# GPIO_mcu_plis.net
KiCad netlist of a schematic drawn in Altium Designer
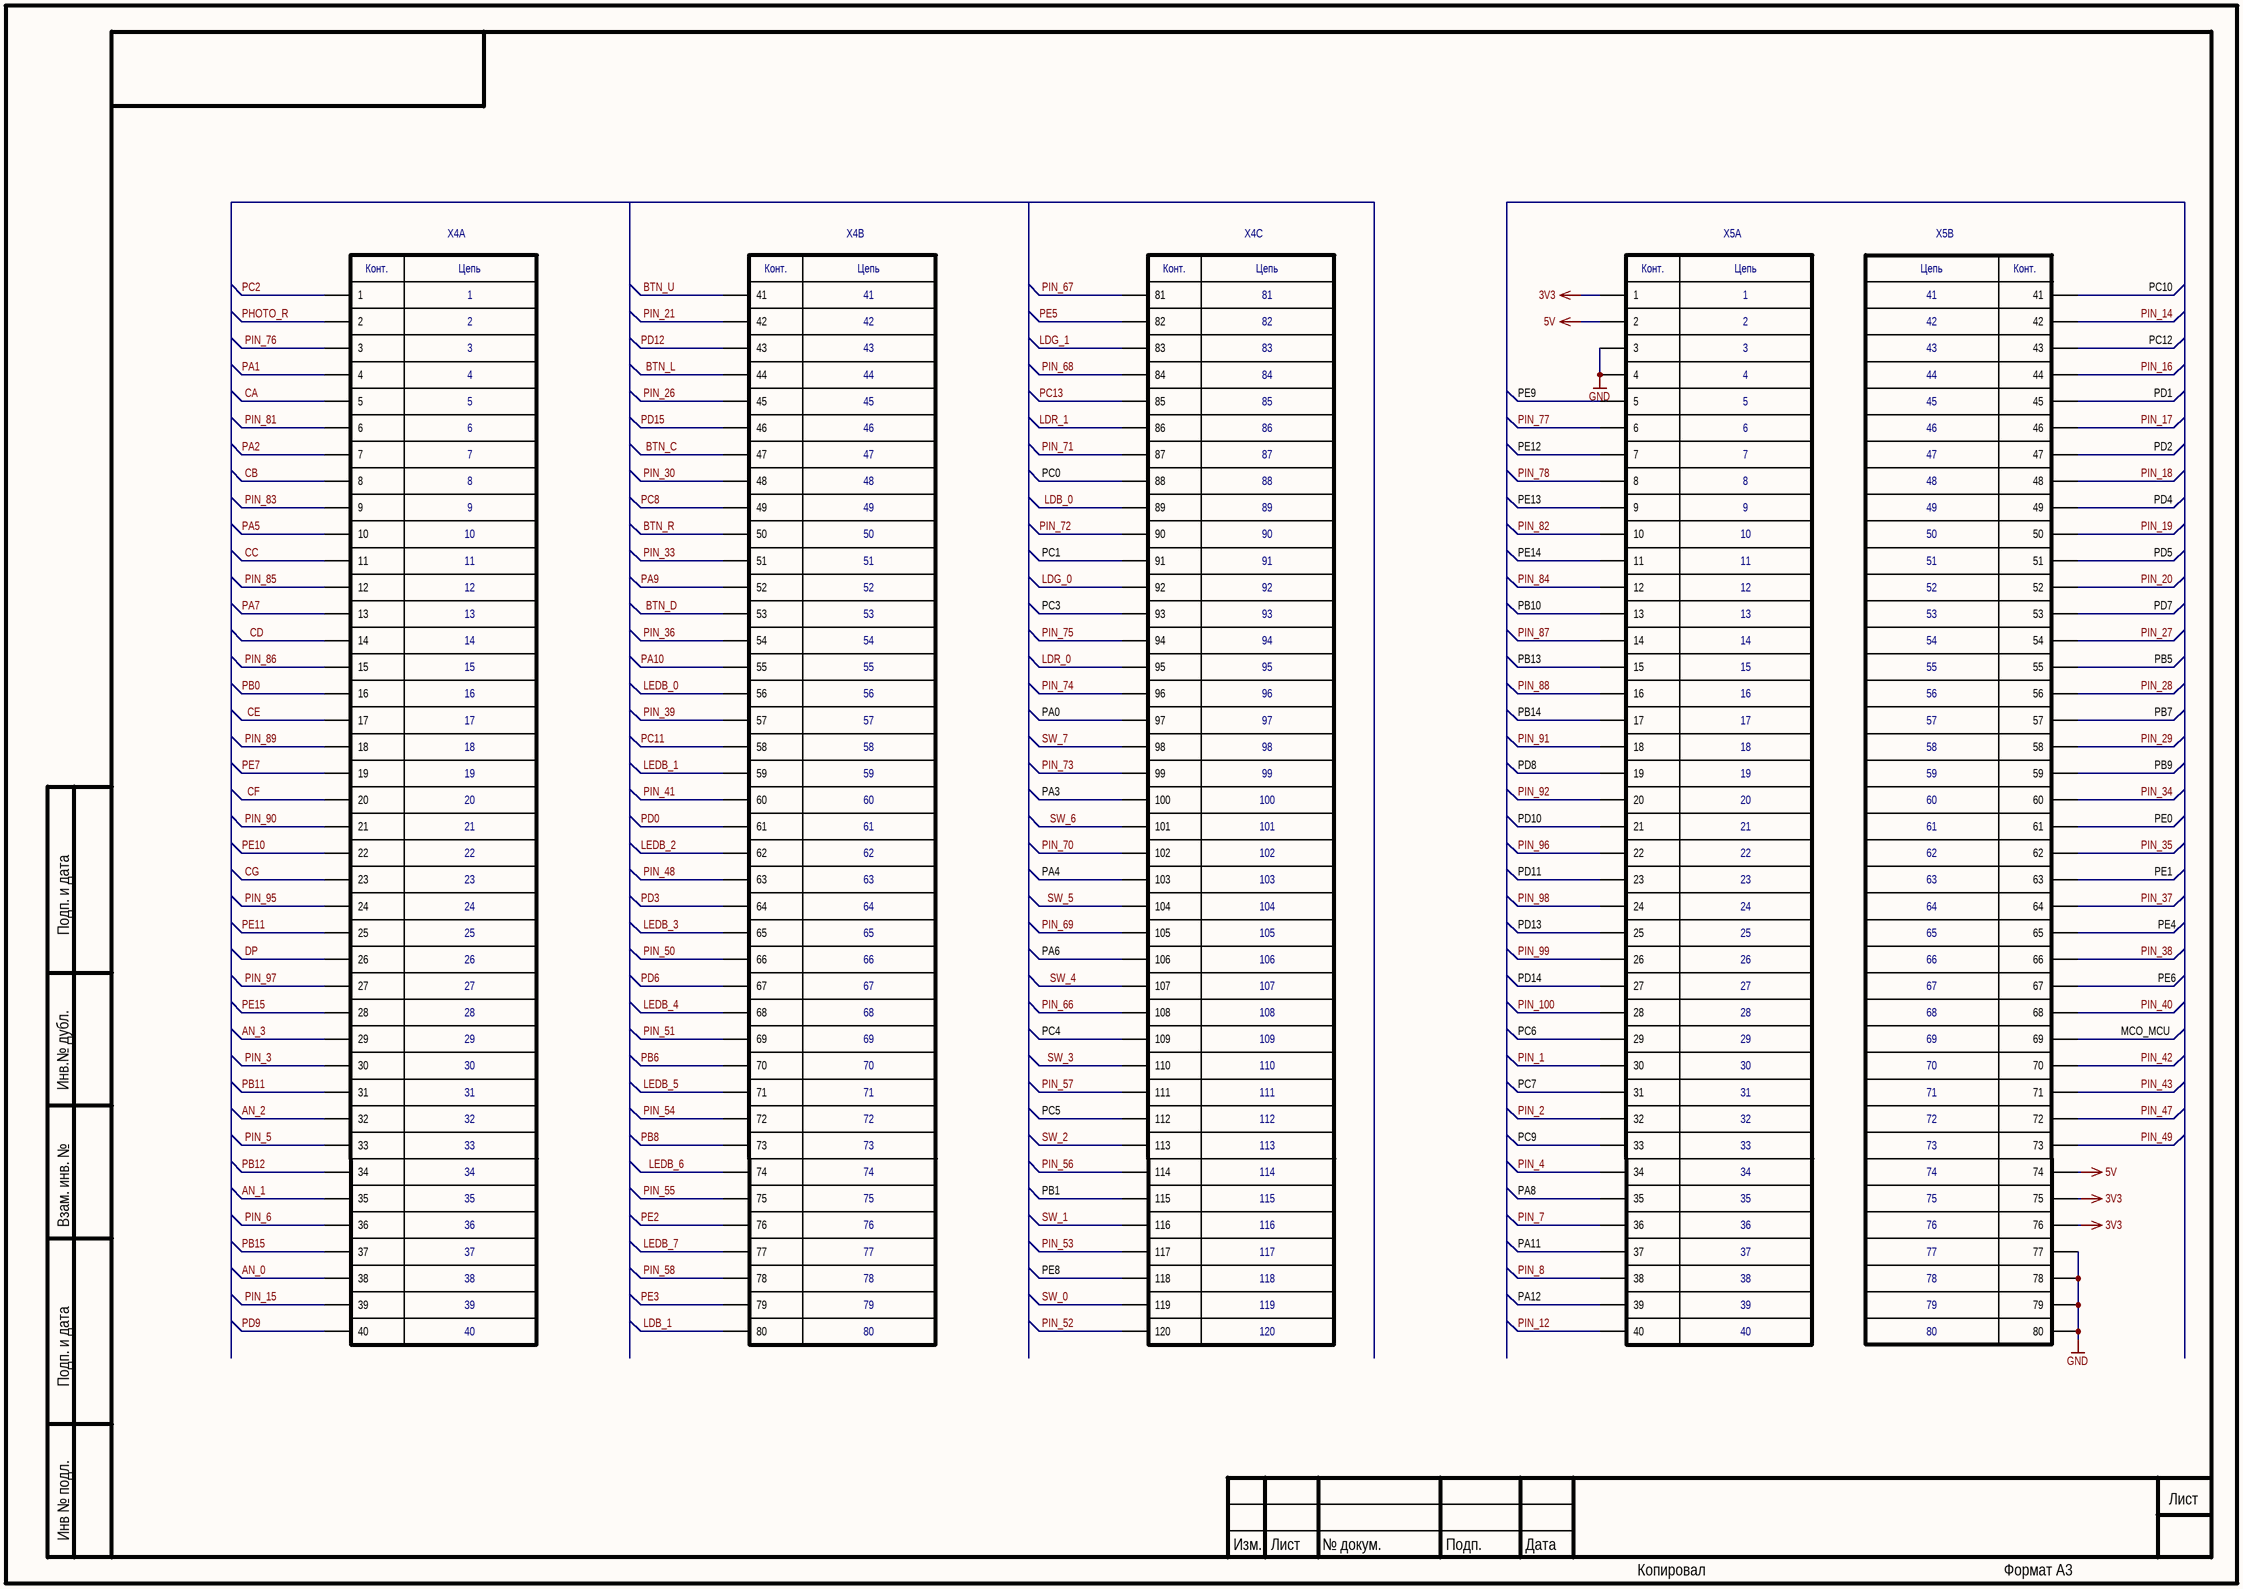
[diagram p0: GPIO_mcu_plis.SchDoc]

(export (version "E")
  (design (tool "Eeschema 10.0.6"))
  (components
    (comp (ref "X4")
      (value "KONT_POLE_MEZ")
      (footprint "Lisaveta_PCB:PLT-120")
      (libsource (lib "Lisaveta") (part "KONT_POLE_120"))
    )
    (comp (ref "X5")
      (value "KONT_POLE_MEZ")
      (footprint "PLD-80")
      (libsource (lib "Lisaveta") (part "KONT_POLE_80"))
    )
  )
  (nets
    (net (code "1") (name "/AN_0") (class "Default")
      (node (ref "X4") (pin "38") (pinfunction "38_38") (pintype "passive"))
    )
    (net (code "2") (name "/AN_1") (class "Default")
      (node (ref "X4") (pin "35") (pinfunction "35_35") (pintype "passive"))
    )
    (net (code "3") (name "/AN_2") (class "Default")
      (node (ref "X4") (pin "32") (pinfunction "32_32") (pintype "passive"))
    )
    (net (code "4") (name "/AN_3") (class "Default")
      (node (ref "X4") (pin "29") (pinfunction "29_29") (pintype "passive"))
    )
    (net (code "5") (name "/BTN_C") (class "Default")
      (node (ref "X4") (pin "47") (pinfunction "47_47") (pintype "passive"))
    )
    (net (code "6") (name "/BTN_D") (class "Default")
      (node (ref "X4") (pin "53") (pinfunction "53_53") (pintype "passive"))
    )
    (net (code "7") (name "/BTN_L") (class "Default")
      (node (ref "X4") (pin "44") (pinfunction "44_44") (pintype "passive"))
    )
    (net (code "8") (name "/BTN_R") (class "Default")
      (node (ref "X4") (pin "50") (pinfunction "50_50") (pintype "passive"))
    )
    (net (code "9") (name "/BTN_U") (class "Default")
      (node (ref "X4") (pin "41") (pinfunction "41_41") (pintype "passive"))
    )
    (net (code "10") (name "/CA") (class "Default")
      (node (ref "X4") (pin "5") (pinfunction "5_5") (pintype "passive"))
    )
    (net (code "11") (name "/CB") (class "Default")
      (node (ref "X4") (pin "8") (pinfunction "8_8") (pintype "passive"))
    )
    (net (code "12") (name "/CC") (class "Default")
      (node (ref "X4") (pin "11") (pinfunction "11_11") (pintype "passive"))
    )
    (net (code "13") (name "/CD") (class "Default")
      (node (ref "X4") (pin "14") (pinfunction "14_14") (pintype "passive"))
    )
    (net (code "14") (name "/CE") (class "Default")
      (node (ref "X4") (pin "17") (pinfunction "17_17") (pintype "passive"))
    )
    (net (code "15") (name "/CF") (class "Default")
      (node (ref "X4") (pin "20") (pinfunction "20_20") (pintype "passive"))
    )
    (net (code "16") (name "/CG") (class "Default")
      (node (ref "X4") (pin "23") (pinfunction "23_23") (pintype "passive"))
    )
    (net (code "17") (name "/DP") (class "Default")
      (node (ref "X4") (pin "26") (pinfunction "26_26") (pintype "passive"))
    )
    (net (code "18") (name "/LDB_0") (class "Default")
      (node (ref "X4") (pin "89") (pinfunction "89_89") (pintype "passive"))
    )
    (net (code "19") (name "/LDB_1") (class "Default")
      (node (ref "X4") (pin "80") (pinfunction "80_80") (pintype "passive"))
    )
    (net (code "20") (name "/LDG_0") (class "Default")
      (node (ref "X4") (pin "92") (pinfunction "92_92") (pintype "passive"))
    )
    (net (code "21") (name "/LDG_1") (class "Default")
      (node (ref "X4") (pin "83") (pinfunction "83_83") (pintype "passive"))
    )
    (net (code "22") (name "/LDR_0") (class "Default")
      (node (ref "X4") (pin "95") (pinfunction "95_95") (pintype "passive"))
    )
    (net (code "23") (name "/LDR_1") (class "Default")
      (node (ref "X4") (pin "86") (pinfunction "86_86") (pintype "passive"))
    )
    (net (code "24") (name "/LEDB_0") (class "Default")
      (node (ref "X4") (pin "56") (pinfunction "56_56") (pintype "passive"))
    )
    (net (code "25") (name "/LEDB_1") (class "Default")
      (node (ref "X4") (pin "59") (pinfunction "59_59") (pintype "passive"))
    )
    (net (code "26") (name "/LEDB_2") (class "Default")
      (node (ref "X4") (pin "62") (pinfunction "62_62") (pintype "passive"))
    )
    (net (code "27") (name "/LEDB_3") (class "Default")
      (node (ref "X4") (pin "65") (pinfunction "65_65") (pintype "passive"))
    )
    (net (code "28") (name "/LEDB_4") (class "Default")
      (node (ref "X4") (pin "68") (pinfunction "68_68") (pintype "passive"))
    )
    (net (code "29") (name "/LEDB_5") (class "Default")
      (node (ref "X4") (pin "71") (pinfunction "71_71") (pintype "passive"))
    )
    (net (code "30") (name "/LEDB_6") (class "Default")
      (node (ref "X4") (pin "74") (pinfunction "74_74") (pintype "passive"))
    )
    (net (code "31") (name "/LEDB_7") (class "Default")
      (node (ref "X4") (pin "77") (pinfunction "77_77") (pintype "passive"))
    )
    (net (code "32") (name "/MCO_MCU") (class "Default")
      (node (ref "X5") (pin "69") (pinfunction "69_69") (pintype "passive"))
    )
    (net (code "33") (name "/PA0") (class "Default")
      (node (ref "X4") (pin "97") (pinfunction "97_97") (pintype "passive"))
    )
    (net (code "34") (name "/PA1") (class "Default")
      (node (ref "X4") (pin "4") (pinfunction "4_4") (pintype "passive"))
    )
    (net (code "35") (name "/PA2") (class "Default")
      (node (ref "X4") (pin "7") (pinfunction "7_7") (pintype "passive"))
    )
    (net (code "36") (name "/PA3") (class "Default")
      (node (ref "X4") (pin "100") (pinfunction "100_100") (pintype "passive"))
    )
    (net (code "37") (name "/PA4") (class "Default")
      (node (ref "X4") (pin "103") (pinfunction "103_103") (pintype "passive"))
    )
    (net (code "38") (name "/PA5") (class "Default")
      (node (ref "X4") (pin "10") (pinfunction "10_10") (pintype "passive"))
    )
    (net (code "39") (name "/PA6") (class "Default")
      (node (ref "X4") (pin "106") (pinfunction "106_106") (pintype "passive"))
    )
    (net (code "40") (name "/PA7") (class "Default")
      (node (ref "X4") (pin "13") (pinfunction "13_13") (pintype "passive"))
    )
    (net (code "41") (name "/PA8") (class "Default")
      (node (ref "X5") (pin "35") (pinfunction "35_35") (pintype "passive"))
    )
    (net (code "42") (name "/PA9") (class "Default")
      (node (ref "X4") (pin "52") (pinfunction "52_52") (pintype "passive"))
    )
    (net (code "43") (name "/PA10") (class "Default")
      (node (ref "X4") (pin "55") (pinfunction "55_55") (pintype "passive"))
    )
    (net (code "44") (name "/PA11") (class "Default")
      (node (ref "X5") (pin "37") (pinfunction "37_37") (pintype "passive"))
    )
    (net (code "45") (name "/PA12") (class "Default")
      (node (ref "X5") (pin "39") (pinfunction "39_39") (pintype "passive"))
    )
    (net (code "46") (name "/PB0") (class "Default")
      (node (ref "X4") (pin "16") (pinfunction "16_16") (pintype "passive"))
    )
    (net (code "47") (name "/PB1") (class "Default")
      (node (ref "X4") (pin "115") (pinfunction "115_115") (pintype "passive"))
    )
    (net (code "48") (name "/PB5") (class "Default")
      (node (ref "X5") (pin "55") (pinfunction "55_55") (pintype "passive"))
    )
    (net (code "49") (name "/PB6") (class "Default")
      (node (ref "X4") (pin "70") (pinfunction "70_70") (pintype "passive"))
    )
    (net (code "50") (name "/PB7") (class "Default")
      (node (ref "X5") (pin "57") (pinfunction "57_57") (pintype "passive"))
    )
    (net (code "51") (name "/PB8") (class "Default")
      (node (ref "X4") (pin "73") (pinfunction "73_73") (pintype "passive"))
    )
    (net (code "52") (name "/PB9") (class "Default")
      (node (ref "X5") (pin "59") (pinfunction "59_59") (pintype "passive"))
    )
    (net (code "53") (name "/PB10") (class "Default")
      (node (ref "X5") (pin "13") (pinfunction "13_13") (pintype "passive"))
    )
    (net (code "54") (name "/PB11") (class "Default")
      (node (ref "X4") (pin "31") (pinfunction "31_31") (pintype "passive"))
    )
    (net (code "55") (name "/PB12") (class "Default")
      (node (ref "X4") (pin "34") (pinfunction "34_34") (pintype "passive"))
    )
    (net (code "56") (name "/PB13") (class "Default")
      (node (ref "X5") (pin "15") (pinfunction "15_15") (pintype "passive"))
    )
    (net (code "57") (name "/PB14") (class "Default")
      (node (ref "X5") (pin "17") (pinfunction "17_17") (pintype "passive"))
    )
    (net (code "58") (name "/PB15") (class "Default")
      (node (ref "X4") (pin "37") (pinfunction "37_37") (pintype "passive"))
    )
    (net (code "59") (name "/PC0") (class "Default")
      (node (ref "X4") (pin "88") (pinfunction "88_88") (pintype "passive"))
    )
    (net (code "60") (name "/PC1") (class "Default")
      (node (ref "X4") (pin "91") (pinfunction "91_91") (pintype "passive"))
    )
    (net (code "61") (name "/PC2") (class "Default")
      (node (ref "X4") (pin "1") (pinfunction "1_1") (pintype "passive"))
    )
    (net (code "62") (name "/PC3") (class "Default")
      (node (ref "X4") (pin "93") (pinfunction "93_93") (pintype "passive"))
    )
    (net (code "63") (name "/PC4") (class "Default")
      (node (ref "X4") (pin "109") (pinfunction "109_109") (pintype "passive"))
    )
    (net (code "64") (name "/PC5") (class "Default")
      (node (ref "X4") (pin "112") (pinfunction "112_112") (pintype "passive"))
    )
    (net (code "65") (name "/PC6") (class "Default")
      (node (ref "X5") (pin "29") (pinfunction "29_29") (pintype "passive"))
    )
    (net (code "66") (name "/PC7") (class "Default")
      (node (ref "X5") (pin "31") (pinfunction "31_31") (pintype "passive"))
    )
    (net (code "67") (name "/PC8") (class "Default")
      (node (ref "X4") (pin "49") (pinfunction "49_49") (pintype "passive"))
    )
    (net (code "68") (name "/PC9") (class "Default")
      (node (ref "X5") (pin "33") (pinfunction "33_33") (pintype "passive"))
    )
    (net (code "69") (name "/PC10") (class "Default")
      (node (ref "X5") (pin "41") (pinfunction "41_41") (pintype "passive"))
    )
    (net (code "70") (name "/PC11") (class "Default")
      (node (ref "X4") (pin "58") (pinfunction "58_58") (pintype "passive"))
    )
    (net (code "71") (name "/PC12") (class "Default")
      (node (ref "X5") (pin "43") (pinfunction "43_43") (pintype "passive"))
    )
    (net (code "72") (name "/PC13") (class "Default")
      (node (ref "X4") (pin "85") (pinfunction "85_85") (pintype "passive"))
    )
    (net (code "73") (name "/PD0") (class "Default")
      (node (ref "X4") (pin "61") (pinfunction "61_61") (pintype "passive"))
    )
    (net (code "74") (name "/PD1") (class "Default")
      (node (ref "X5") (pin "45") (pinfunction "45_45") (pintype "passive"))
    )
    (net (code "75") (name "/PD2") (class "Default")
      (node (ref "X5") (pin "47") (pinfunction "47_47") (pintype "passive"))
    )
    (net (code "76") (name "/PD3") (class "Default")
      (node (ref "X4") (pin "64") (pinfunction "64_64") (pintype "passive"))
    )
    (net (code "77") (name "/PD4") (class "Default")
      (node (ref "X5") (pin "49") (pinfunction "49_49") (pintype "passive"))
    )
    (net (code "78") (name "/PD5") (class "Default")
      (node (ref "X5") (pin "51") (pinfunction "51_51") (pintype "passive"))
    )
    (net (code "79") (name "/PD6") (class "Default")
      (node (ref "X4") (pin "67") (pinfunction "67_67") (pintype "passive"))
    )
    (net (code "80") (name "/PD7") (class "Default")
      (node (ref "X5") (pin "53") (pinfunction "53_53") (pintype "passive"))
    )
    (net (code "81") (name "/PD8") (class "Default")
      (node (ref "X5") (pin "19") (pinfunction "19_19") (pintype "passive"))
    )
    (net (code "82") (name "/PD9") (class "Default")
      (node (ref "X4") (pin "40") (pinfunction "40_40") (pintype "passive"))
    )
    (net (code "83") (name "/PD10") (class "Default")
      (node (ref "X5") (pin "21") (pinfunction "21_21") (pintype "passive"))
    )
    (net (code "84") (name "/PD11") (class "Default")
      (node (ref "X5") (pin "23") (pinfunction "23_23") (pintype "passive"))
    )
    (net (code "85") (name "/PD12") (class "Default")
      (node (ref "X4") (pin "43") (pinfunction "43_43") (pintype "passive"))
    )
    (net (code "86") (name "/PD13") (class "Default")
      (node (ref "X5") (pin "25") (pinfunction "25_25") (pintype "passive"))
    )
    (net (code "87") (name "/PD14") (class "Default")
      (node (ref "X5") (pin "27") (pinfunction "27_27") (pintype "passive"))
    )
    (net (code "88") (name "/PD15") (class "Default")
      (node (ref "X4") (pin "46") (pinfunction "46_46") (pintype "passive"))
    )
    (net (code "89") (name "/PE0") (class "Default")
      (node (ref "X5") (pin "61") (pinfunction "61_61") (pintype "passive"))
    )
    (net (code "90") (name "/PE1") (class "Default")
      (node (ref "X5") (pin "63") (pinfunction "63_63") (pintype "passive"))
    )
    (net (code "91") (name "/PE2") (class "Default")
      (node (ref "X4") (pin "76") (pinfunction "76_76") (pintype "passive"))
    )
    (net (code "92") (name "/PE3") (class "Default")
      (node (ref "X4") (pin "79") (pinfunction "79_79") (pintype "passive"))
    )
    (net (code "93") (name "/PE4") (class "Default")
      (node (ref "X5") (pin "65") (pinfunction "65_65") (pintype "passive"))
    )
    (net (code "94") (name "/PE5") (class "Default")
      (node (ref "X4") (pin "82") (pinfunction "82_82") (pintype "passive"))
    )
    (net (code "95") (name "/PE6") (class "Default")
      (node (ref "X5") (pin "67") (pinfunction "67_67") (pintype "passive"))
    )
    (net (code "96") (name "/PE7") (class "Default")
      (node (ref "X4") (pin "19") (pinfunction "19_19") (pintype "passive"))
    )
    (net (code "97") (name "/PE8") (class "Default")
      (node (ref "X4") (pin "118") (pinfunction "118_118") (pintype "passive"))
    )
    (net (code "98") (name "/PE9") (class "Default")
      (node (ref "X5") (pin "5") (pinfunction "5_5") (pintype "passive"))
    )
    (net (code "99") (name "/PE10") (class "Default")
      (node (ref "X4") (pin "22") (pinfunction "22_22") (pintype "passive"))
    )
    (net (code "100") (name "/PE11") (class "Default")
      (node (ref "X4") (pin "25") (pinfunction "25_25") (pintype "passive"))
    )
    (net (code "101") (name "/PE12") (class "Default")
      (node (ref "X5") (pin "7") (pinfunction "7_7") (pintype "passive"))
    )
    (net (code "102") (name "/PE13") (class "Default")
      (node (ref "X5") (pin "9") (pinfunction "9_9") (pintype "passive"))
    )
    (net (code "103") (name "/PE14") (class "Default")
      (node (ref "X5") (pin "11") (pinfunction "11_11") (pintype "passive"))
    )
    (net (code "104") (name "/PE15") (class "Default")
      (node (ref "X4") (pin "28") (pinfunction "28_28") (pintype "passive"))
    )
    (net (code "105") (name "/PHOTO_R") (class "Default")
      (node (ref "X4") (pin "2") (pinfunction "2_2") (pintype "passive"))
    )
    (net (code "106") (name "/PIN_1") (class "Default")
      (node (ref "X5") (pin "30") (pinfunction "30_30") (pintype "passive"))
    )
    (net (code "107") (name "/PIN_2") (class "Default")
      (node (ref "X5") (pin "32") (pinfunction "32_32") (pintype "passive"))
    )
    (net (code "108") (name "/PIN_3") (class "Default")
      (node (ref "X4") (pin "30") (pinfunction "30_30") (pintype "passive"))
    )
    (net (code "109") (name "/PIN_4") (class "Default")
      (node (ref "X5") (pin "34") (pinfunction "34_34") (pintype "passive"))
    )
    (net (code "110") (name "/PIN_5") (class "Default")
      (node (ref "X4") (pin "33") (pinfunction "33_33") (pintype "passive"))
    )
    (net (code "111") (name "/PIN_6") (class "Default")
      (node (ref "X4") (pin "36") (pinfunction "36_36") (pintype "passive"))
    )
    (net (code "112") (name "/PIN_7") (class "Default")
      (node (ref "X5") (pin "36") (pinfunction "36_36") (pintype "passive"))
    )
    (net (code "113") (name "/PIN_8") (class "Default")
      (node (ref "X5") (pin "38") (pinfunction "38_38") (pintype "passive"))
    )
    (net (code "114") (name "/PIN_12") (class "Default")
      (node (ref "X5") (pin "40") (pinfunction "40_40") (pintype "passive"))
    )
    (net (code "115") (name "/PIN_14") (class "Default")
      (node (ref "X5") (pin "42") (pinfunction "42_42") (pintype "passive"))
    )
    (net (code "116") (name "/PIN_15") (class "Default")
      (node (ref "X4") (pin "39") (pinfunction "39_39") (pintype "passive"))
    )
    (net (code "117") (name "/PIN_16") (class "Default")
      (node (ref "X5") (pin "44") (pinfunction "44_44") (pintype "passive"))
    )
    (net (code "118") (name "/PIN_17") (class "Default")
      (node (ref "X5") (pin "46") (pinfunction "46_46") (pintype "passive"))
    )
    (net (code "119") (name "/PIN_18") (class "Default")
      (node (ref "X5") (pin "48") (pinfunction "48_48") (pintype "passive"))
    )
    (net (code "120") (name "/PIN_19") (class "Default")
      (node (ref "X5") (pin "50") (pinfunction "50_50") (pintype "passive"))
    )
    (net (code "121") (name "/PIN_20") (class "Default")
      (node (ref "X5") (pin "52") (pinfunction "52_52") (pintype "passive"))
    )
    (net (code "122") (name "/PIN_21") (class "Default")
      (node (ref "X4") (pin "42") (pinfunction "42_42") (pintype "passive"))
    )
    (net (code "123") (name "/PIN_26") (class "Default")
      (node (ref "X4") (pin "45") (pinfunction "45_45") (pintype "passive"))
    )
    (net (code "124") (name "/PIN_27") (class "Default")
      (node (ref "X5") (pin "54") (pinfunction "54_54") (pintype "passive"))
    )
    (net (code "125") (name "/PIN_28") (class "Default")
      (node (ref "X5") (pin "56") (pinfunction "56_56") (pintype "passive"))
    )
    (net (code "126") (name "/PIN_29") (class "Default")
      (node (ref "X5") (pin "58") (pinfunction "58_58") (pintype "passive"))
    )
    (net (code "127") (name "/PIN_30") (class "Default")
      (node (ref "X4") (pin "48") (pinfunction "48_48") (pintype "passive"))
    )
    (net (code "128") (name "/PIN_33") (class "Default")
      (node (ref "X4") (pin "51") (pinfunction "51_51") (pintype "passive"))
    )
    (net (code "129") (name "/PIN_34") (class "Default")
      (node (ref "X5") (pin "60") (pinfunction "60_60") (pintype "passive"))
    )
    (net (code "130") (name "/PIN_35") (class "Default")
      (node (ref "X5") (pin "62") (pinfunction "62_62") (pintype "passive"))
    )
    (net (code "131") (name "/PIN_36") (class "Default")
      (node (ref "X4") (pin "54") (pinfunction "54_54") (pintype "passive"))
    )
    (net (code "132") (name "/PIN_37") (class "Default")
      (node (ref "X5") (pin "64") (pinfunction "64_64") (pintype "passive"))
    )
    (net (code "133") (name "/PIN_38") (class "Default")
      (node (ref "X5") (pin "66") (pinfunction "66_66") (pintype "passive"))
    )
    (net (code "134") (name "/PIN_39") (class "Default")
      (node (ref "X4") (pin "57") (pinfunction "57_57") (pintype "passive"))
    )
    (net (code "135") (name "/PIN_40") (class "Default")
      (node (ref "X5") (pin "68") (pinfunction "68_68") (pintype "passive"))
    )
    (net (code "136") (name "/PIN_41") (class "Default")
      (node (ref "X4") (pin "60") (pinfunction "60_60") (pintype "passive"))
    )
    (net (code "137") (name "/PIN_42") (class "Default")
      (node (ref "X5") (pin "70") (pinfunction "70_70") (pintype "passive"))
    )
    (net (code "138") (name "/PIN_43") (class "Default")
      (node (ref "X5") (pin "71") (pinfunction "71_71") (pintype "passive"))
    )
    (net (code "139") (name "/PIN_47") (class "Default")
      (node (ref "X5") (pin "72") (pinfunction "72_72") (pintype "passive"))
    )
    (net (code "140") (name "/PIN_48") (class "Default")
      (node (ref "X4") (pin "63") (pinfunction "63_63") (pintype "passive"))
    )
    (net (code "141") (name "/PIN_49") (class "Default")
      (node (ref "X5") (pin "73") (pinfunction "73_73") (pintype "passive"))
    )
    (net (code "142") (name "/PIN_50") (class "Default")
      (node (ref "X4") (pin "66") (pinfunction "66_66") (pintype "passive"))
    )
    (net (code "143") (name "/PIN_51") (class "Default")
      (node (ref "X4") (pin "69") (pinfunction "69_69") (pintype "passive"))
    )
    (net (code "144") (name "/PIN_52") (class "Default")
      (node (ref "X4") (pin "120") (pinfunction "120_120") (pintype "passive"))
    )
    (net (code "145") (name "/PIN_53") (class "Default")
      (node (ref "X4") (pin "117") (pinfunction "117_117") (pintype "passive"))
    )
    (net (code "146") (name "/PIN_54") (class "Default")
      (node (ref "X4") (pin "72") (pinfunction "72_72") (pintype "passive"))
    )
    (net (code "147") (name "/PIN_55") (class "Default")
      (node (ref "X4") (pin "75") (pinfunction "75_75") (pintype "passive"))
    )
    (net (code "148") (name "/PIN_56") (class "Default")
      (node (ref "X4") (pin "114") (pinfunction "114_114") (pintype "passive"))
    )
    (net (code "149") (name "/PIN_57") (class "Default")
      (node (ref "X4") (pin "111") (pinfunction "111_111") (pintype "passive"))
    )
    (net (code "150") (name "/PIN_58") (class "Default")
      (node (ref "X4") (pin "78") (pinfunction "78_78") (pintype "passive"))
    )
    (net (code "151") (name "/PIN_66") (class "Default")
      (node (ref "X4") (pin "108") (pinfunction "108_108") (pintype "passive"))
    )
    (net (code "152") (name "/PIN_67") (class "Default")
      (node (ref "X4") (pin "81") (pinfunction "81_81") (pintype "passive"))
    )
    (net (code "153") (name "/PIN_68") (class "Default")
      (node (ref "X4") (pin "84") (pinfunction "84_84") (pintype "passive"))
    )
    (net (code "154") (name "/PIN_69") (class "Default")
      (node (ref "X4") (pin "105") (pinfunction "105_105") (pintype "passive"))
    )
    (net (code "155") (name "/PIN_70") (class "Default")
      (node (ref "X4") (pin "102") (pinfunction "102_102") (pintype "passive"))
    )
    (net (code "156") (name "/PIN_71") (class "Default")
      (node (ref "X4") (pin "87") (pinfunction "87_87") (pintype "passive"))
    )
    (net (code "157") (name "/PIN_72") (class "Default")
      (node (ref "X4") (pin "90") (pinfunction "90_90") (pintype "passive"))
    )
    (net (code "158") (name "/PIN_73") (class "Default")
      (node (ref "X4") (pin "99") (pinfunction "99_99") (pintype "passive"))
    )
    (net (code "159") (name "/PIN_74") (class "Default")
      (node (ref "X4") (pin "96") (pinfunction "96_96") (pintype "passive"))
    )
    (net (code "160") (name "/PIN_75") (class "Default")
      (node (ref "X4") (pin "94") (pinfunction "94_94") (pintype "passive"))
    )
    (net (code "161") (name "/PIN_76") (class "Default")
      (node (ref "X4") (pin "3") (pinfunction "3_3") (pintype "passive"))
    )
    (net (code "162") (name "/PIN_77") (class "Default")
      (node (ref "X5") (pin "6") (pinfunction "6_6") (pintype "passive"))
    )
    (net (code "163") (name "/PIN_78") (class "Default")
      (node (ref "X5") (pin "8") (pinfunction "8_8") (pintype "passive"))
    )
    (net (code "164") (name "/PIN_81") (class "Default")
      (node (ref "X4") (pin "6") (pinfunction "6_6") (pintype "passive"))
    )
    (net (code "165") (name "/PIN_82") (class "Default")
      (node (ref "X5") (pin "10") (pinfunction "10_10") (pintype "passive"))
    )
    (net (code "166") (name "/PIN_83") (class "Default")
      (node (ref "X4") (pin "9") (pinfunction "9_9") (pintype "passive"))
    )
    (net (code "167") (name "/PIN_84") (class "Default")
      (node (ref "X5") (pin "12") (pinfunction "12_12") (pintype "passive"))
    )
    (net (code "168") (name "/PIN_85") (class "Default")
      (node (ref "X4") (pin "12") (pinfunction "12_12") (pintype "passive"))
    )
    (net (code "169") (name "/PIN_86") (class "Default")
      (node (ref "X4") (pin "15") (pinfunction "15_15") (pintype "passive"))
    )
    (net (code "170") (name "/PIN_87") (class "Default")
      (node (ref "X5") (pin "14") (pinfunction "14_14") (pintype "passive"))
    )
    (net (code "171") (name "/PIN_88") (class "Default")
      (node (ref "X5") (pin "16") (pinfunction "16_16") (pintype "passive"))
    )
    (net (code "172") (name "/PIN_89") (class "Default")
      (node (ref "X4") (pin "18") (pinfunction "18_18") (pintype "passive"))
    )
    (net (code "173") (name "/PIN_90") (class "Default")
      (node (ref "X4") (pin "21") (pinfunction "21_21") (pintype "passive"))
    )
    (net (code "174") (name "/PIN_91") (class "Default")
      (node (ref "X5") (pin "18") (pinfunction "18_18") (pintype "passive"))
    )
    (net (code "175") (name "/PIN_92") (class "Default")
      (node (ref "X5") (pin "20") (pinfunction "20_20") (pintype "passive"))
    )
    (net (code "176") (name "/PIN_95") (class "Default")
      (node (ref "X4") (pin "24") (pinfunction "24_24") (pintype "passive"))
    )
    (net (code "177") (name "/PIN_96") (class "Default")
      (node (ref "X5") (pin "22") (pinfunction "22_22") (pintype "passive"))
    )
    (net (code "178") (name "/PIN_97") (class "Default")
      (node (ref "X4") (pin "27") (pinfunction "27_27") (pintype "passive"))
    )
    (net (code "179") (name "/PIN_98") (class "Default")
      (node (ref "X5") (pin "24") (pinfunction "24_24") (pintype "passive"))
    )
    (net (code "180") (name "/PIN_99") (class "Default")
      (node (ref "X5") (pin "26") (pinfunction "26_26") (pintype "passive"))
    )
    (net (code "181") (name "/PIN_100") (class "Default")
      (node (ref "X5") (pin "28") (pinfunction "28_28") (pintype "passive"))
    )
    (net (code "182") (name "/SW_0") (class "Default")
      (node (ref "X4") (pin "119") (pinfunction "119_119") (pintype "passive"))
    )
    (net (code "183") (name "/SW_1") (class "Default")
      (node (ref "X4") (pin "116") (pinfunction "116_116") (pintype "passive"))
    )
    (net (code "184") (name "/SW_2") (class "Default")
      (node (ref "X4") (pin "113") (pinfunction "113_113") (pintype "passive"))
    )
    (net (code "185") (name "/SW_3") (class "Default")
      (node (ref "X4") (pin "110") (pinfunction "110_110") (pintype "passive"))
    )
    (net (code "186") (name "/SW_4") (class "Default")
      (node (ref "X4") (pin "107") (pinfunction "107_107") (pintype "passive"))
    )
    (net (code "187") (name "/SW_5") (class "Default")
      (node (ref "X4") (pin "104") (pinfunction "104_104") (pintype "passive"))
    )
    (net (code "188") (name "/SW_6") (class "Default")
      (node (ref "X4") (pin "101") (pinfunction "101_101") (pintype "passive"))
    )
    (net (code "189") (name "/SW_7") (class "Default")
      (node (ref "X4") (pin "98") (pinfunction "98_98") (pintype "passive"))
    )
    (net (code "190") (name "3V3") (class "Default")
      (node (ref "X5") (pin "1") (pinfunction "1_1") (pintype "passive"))
      (node (ref "X5") (pin "75") (pinfunction "75_75") (pintype "passive"))
      (node (ref "X5") (pin "76") (pinfunction "76_76") (pintype "passive"))
    )
    (net (code "191") (name "5V") (class "Default")
      (node (ref "X5") (pin "2") (pinfunction "2_2") (pintype "passive"))
      (node (ref "X5") (pin "74") (pinfunction "74_74") (pintype "passive"))
    )
    (net (code "192") (name "GND") (class "Default")
      (node (ref "X5") (pin "3") (pinfunction "3_3") (pintype "passive"))
      (node (ref "X5") (pin "4") (pinfunction "4_4") (pintype "passive"))
      (node (ref "X5") (pin "77") (pinfunction "77_77") (pintype "passive"))
      (node (ref "X5") (pin "78") (pinfunction "78_78") (pintype "passive"))
      (node (ref "X5") (pin "79") (pinfunction "79_79") (pintype "passive"))
      (node (ref "X5") (pin "80") (pinfunction "80_80") (pintype "passive"))
    )
  )
)
